# SCH_Lasercutter-Air-Control_2024-07-31.net
KiCad netlist of a schematic drawn in EasyEDA
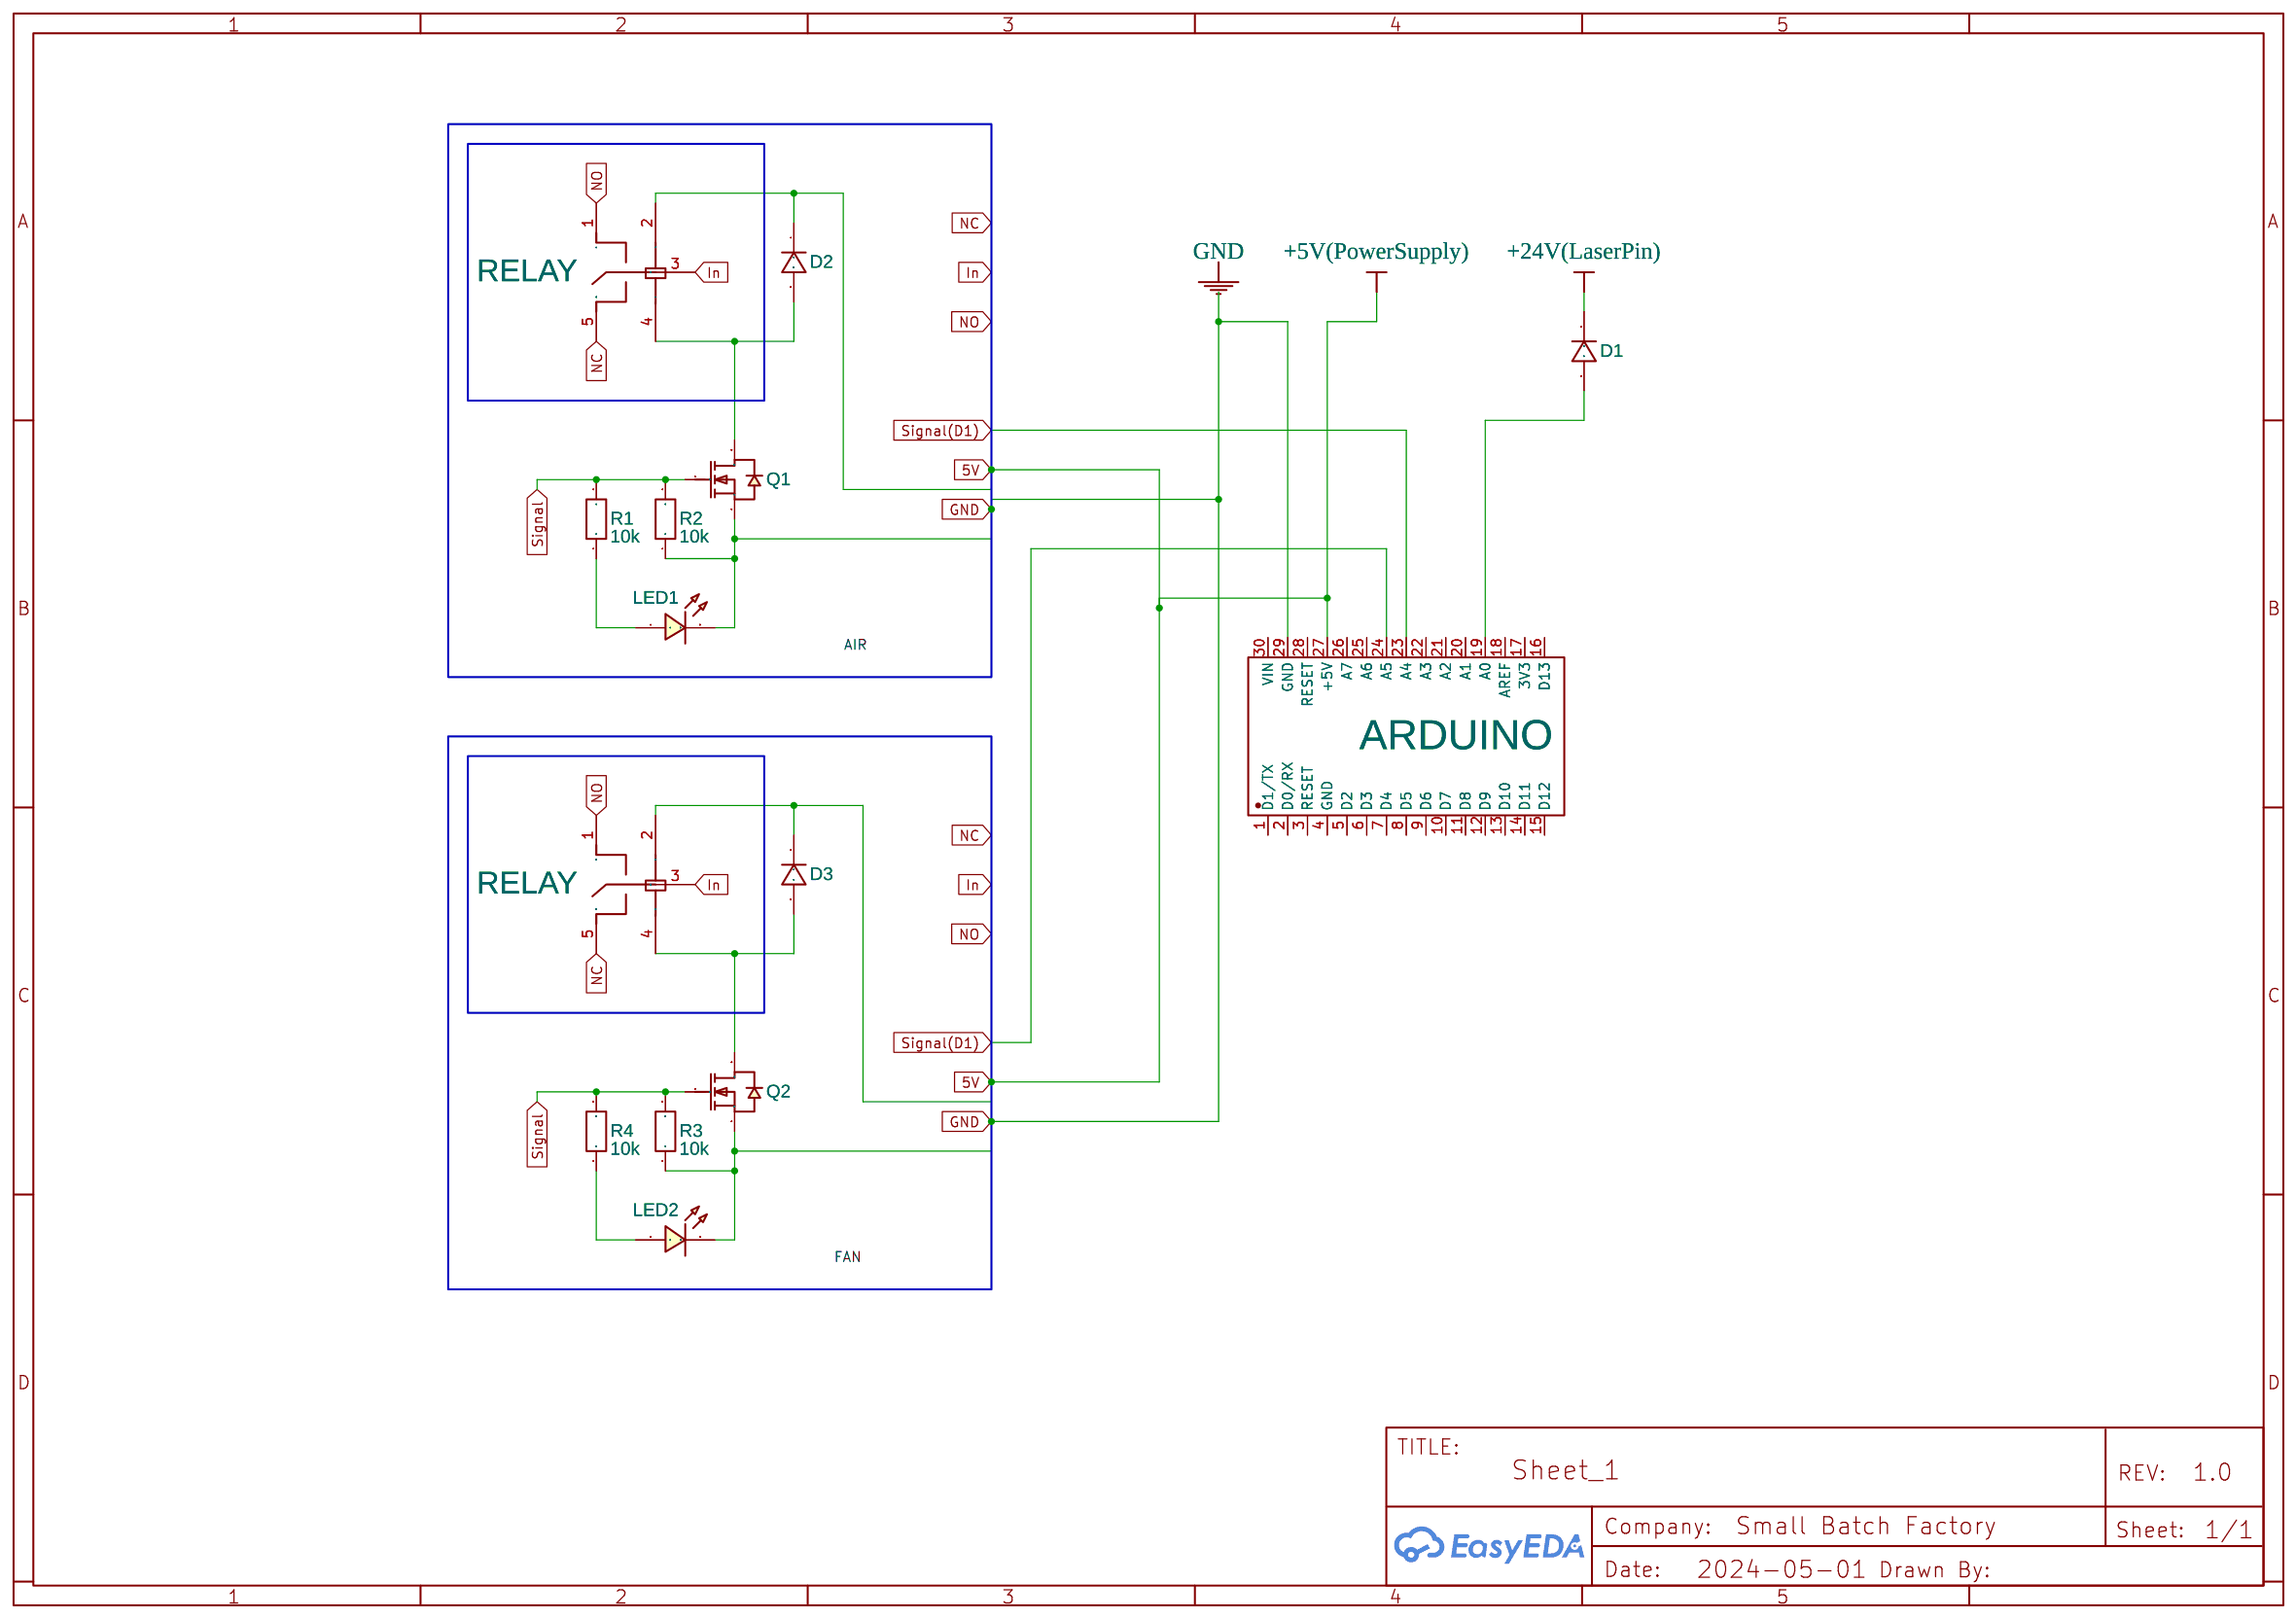
[diagram p0: schematic sheet]

(export (version "E")
  (design (tool "Eeschema 10.0.6"))
  (components
    (comp (ref "ARDUINO") (value "ARDUINO_NANO") (libsource (lib "") (part "ARDUINO_NANO")))
    (comp (ref "D1")
      (value "1N4007W")
      (fields (field (name "Manufacturer") "BLUE ROCKET"))
      (libsource (lib "") (part "1N4007W"))
    )
    (comp (ref "D2")
      (value "1N4007W")
      (fields (field (name "Manufacturer") "BLUE ROCKET"))
      (libsource (lib "") (part "1N4007W"))
    )
    (comp (ref "D3")
      (value "1N4007W")
      (fields (field (name "Manufacturer") "BLUE ROCKET"))
      (libsource (lib "") (part "1N4007W"))
    )
    (comp (ref "LED1")
      (value "LED-0603_R")
      (fields
        (field (name "Manufacturer Part") "19-217/R6C-AL1M2VY/3T")
        (field (name "Manufacturer") "EVERLIGHT(台湾亿光)")
      )
      (libsource (lib "") (part "LED-0603_R"))
    )
    (comp (ref "LED2")
      (value "LED-0603_R")
      (fields
        (field (name "Manufacturer Part") "19-217/R6C-AL1M2VY/3T")
        (field (name "Manufacturer") "EVERLIGHT(台湾亿光)")
      )
      (libsource (lib "") (part "LED-0603_R"))
    )
    (comp (ref "Q1")
      (value "2N7002")
      (fields (field (name "Manufacturer Part") "2N7002,215") (field (name "Manufacturer") "Nexperia"))
      (libsource (lib "") (part "2N7002"))
    )
    (comp (ref "Q2")
      (value "2N7002")
      (fields (field (name "Manufacturer Part") "2N7002,215") (field (name "Manufacturer") "Nexperia"))
      (libsource (lib "") (part "2N7002"))
    )
    (comp (ref "R1") (value "10k") (libsource (lib "") (part "R_0603_EU")))
    (comp (ref "R2") (value "10k") (libsource (lib "") (part "R_0603_EU")))
    (comp (ref "R3") (value "10k") (libsource (lib "") (part "R_0603_EU")))
    (comp (ref "R4") (value "10k") (libsource (lib "") (part "R_0603_EU")))
    (comp (ref "U2")
      (value "RELAY")
      (fields (field (name "Manufacturer Part") "Relay-SPST"))
      (libsource (lib "") (part "RELAY-SPST"))
    )
    (comp (ref "U3")
      (value "RELAY")
      (fields (field (name "Manufacturer Part") "Relay-SPST"))
      (libsource (lib "") (part "RELAY-SPST"))
    )
  )
  (nets
    (net (code "1") (name "+24V(LaserPin)") (class "Default")
      (node (ref "D1") (pin "1") (pinfunction "1_1") (pintype "unspecified"))
    )
    (net (code "4") (name "5V") (class "Default")
      (node (ref "ARDUINO") (pin "27") (pinfunction "+5V_27") (pintype "unspecified"))
      (node (ref "D2") (pin "1") (pinfunction "1_1") (pintype "unspecified"))
      (node (ref "D3") (pin "1") (pinfunction "1_1") (pintype "unspecified"))
      (node (ref "U2") (pin "2") (pinfunction "2_2") (pintype "unspecified"))
      (node (ref "U3") (pin "2") (pinfunction "2_2") (pintype "unspecified"))
    )
    (net (code "5") (name "GND") (class "Default")
      (node (ref "ARDUINO") (pin "29") (pinfunction "GND_29") (pintype "unspecified"))
      (node (ref "LED1") (pin "2") (pinfunction "2_2") (pintype "unspecified"))
      (node (ref "LED2") (pin "2") (pinfunction "2_2") (pintype "unspecified"))
      (node (ref "Q1") (pin "2") (pinfunction "S_2") (pintype "unspecified"))
      (node (ref "Q2") (pin "2") (pinfunction "S_2") (pintype "unspecified"))
      (node (ref "R2") (pin "1") (pinfunction "1_1") (pintype "unspecified"))
      (node (ref "R3") (pin "1") (pinfunction "1_1") (pintype "unspecified"))
    )
    (net (code "6") (name "In") (class "Default")
      (node (ref "U2") (pin "3") (pinfunction "3_3") (pintype "unspecified"))
      (node (ref "U3") (pin "3") (pinfunction "3_3") (pintype "unspecified"))
    )
    (net (code "7") (name "NC") (class "Default")
      (node (ref "U2") (pin "5") (pinfunction "5_5") (pintype "unspecified"))
      (node (ref "U3") (pin "5") (pinfunction "5_5") (pintype "unspecified"))
    )
    (net (code "8") (name "NO") (class "Default")
      (node (ref "U2") (pin "1") (pinfunction "1_1") (pintype "unspecified"))
      (node (ref "U3") (pin "1") (pinfunction "1_1") (pintype "unspecified"))
    )
    (net (code "9") (name "Net-(ARDUINO-A0)") (class "Default")
      (node (ref "ARDUINO") (pin "19") (pinfunction "A0_19") (pintype "unspecified"))
      (node (ref "D1") (pin "2") (pinfunction "2_2") (pintype "unspecified"))
    )
    (net (code "10") (name "Net-(LED1-Pad1)") (class "Default")
      (node (ref "LED1") (pin "1") (pinfunction "1_1") (pintype "unspecified"))
      (node (ref "R1") (pin "1") (pinfunction "1_1") (pintype "unspecified"))
    )
    (net (code "11") (name "Net-(LED2-Pad1)") (class "Default")
      (node (ref "LED2") (pin "1") (pinfunction "1_1") (pintype "unspecified"))
      (node (ref "R4") (pin "1") (pinfunction "1_1") (pintype "unspecified"))
    )
    (net (code "12") (name "Net-(Q1-D)") (class "Default")
      (node (ref "D2") (pin "2") (pinfunction "2_2") (pintype "unspecified"))
      (node (ref "Q1") (pin "3") (pinfunction "D_3") (pintype "unspecified"))
      (node (ref "U2") (pin "4") (pinfunction "4_4") (pintype "unspecified"))
    )
    (net (code "13") (name "Net-(Q2-D)") (class "Default")
      (node (ref "D3") (pin "2") (pinfunction "2_2") (pintype "unspecified"))
      (node (ref "Q2") (pin "3") (pinfunction "D_3") (pintype "unspecified"))
      (node (ref "U3") (pin "4") (pinfunction "4_4") (pintype "unspecified"))
    )
    (net (code "14") (name "Signal") (class "Default")
      (node (ref "Q1") (pin "1") (pinfunction "G_1") (pintype "unspecified"))
      (node (ref "Q2") (pin "1") (pinfunction "G_1") (pintype "unspecified"))
      (node (ref "R1") (pin "2") (pinfunction "2_2") (pintype "unspecified"))
      (node (ref "R2") (pin "2") (pinfunction "2_2") (pintype "unspecified"))
      (node (ref "R3") (pin "2") (pinfunction "2_2") (pintype "unspecified"))
      (node (ref "R4") (pin "2") (pinfunction "2_2") (pintype "unspecified"))
    )
    (net (code "15") (name "Signal(D1)") (class "Default")
      (node (ref "ARDUINO") (pin "23") (pinfunction "A4_23") (pintype "unspecified"))
      (node (ref "ARDUINO") (pin "24") (pinfunction "A5_24") (pintype "unspecified"))
    )
    (net (code "16") (name "unconnected-(ARDUINO-3V3-Pad17)") (class "Default")
      (node (ref "ARDUINO") (pin "17") (pinfunction "3V3_17") (pintype "unspecified"))
    )
    (net (code "17") (name "unconnected-(ARDUINO-A1-Pad20)") (class "Default")
      (node (ref "ARDUINO") (pin "20") (pinfunction "A1_20") (pintype "unspecified"))
    )
    (net (code "18") (name "unconnected-(ARDUINO-A2-Pad21)") (class "Default")
      (node (ref "ARDUINO") (pin "21") (pinfunction "A2_21") (pintype "unspecified"))
    )
    (net (code "19") (name "unconnected-(ARDUINO-A3-Pad22)") (class "Default")
      (node (ref "ARDUINO") (pin "22") (pinfunction "A3_22") (pintype "unspecified"))
    )
    (net (code "20") (name "unconnected-(ARDUINO-A6-Pad25)") (class "Default")
      (node (ref "ARDUINO") (pin "25") (pinfunction "A6_25") (pintype "unspecified"))
    )
    (net (code "21") (name "unconnected-(ARDUINO-A7-Pad26)") (class "Default")
      (node (ref "ARDUINO") (pin "26") (pinfunction "A7_26") (pintype "unspecified"))
    )
    (net (code "22") (name "unconnected-(ARDUINO-AREF-Pad18)") (class "Default")
      (node (ref "ARDUINO") (pin "18") (pinfunction "AREF_18") (pintype "unspecified"))
    )
    (net (code "23") (name "unconnected-(ARDUINO-D0{slash}RX-Pad2)") (class "Default")
      (node (ref "ARDUINO") (pin "2") (pinfunction "D0/RX_2") (pintype "unspecified"))
    )
    (net (code "24") (name "unconnected-(ARDUINO-D1{slash}TX-Pad1)") (class "Default")
      (node (ref "ARDUINO") (pin "1") (pinfunction "D1/TX_1") (pintype "unspecified"))
    )
    (net (code "25") (name "unconnected-(ARDUINO-D2-Pad5)") (class "Default")
      (node (ref "ARDUINO") (pin "5") (pinfunction "D2_5") (pintype "unspecified"))
    )
    (net (code "26") (name "unconnected-(ARDUINO-D3-Pad6)") (class "Default")
      (node (ref "ARDUINO") (pin "6") (pinfunction "D3_6") (pintype "unspecified"))
    )
    (net (code "27") (name "unconnected-(ARDUINO-D4-Pad7)") (class "Default")
      (node (ref "ARDUINO") (pin "7") (pinfunction "D4_7") (pintype "unspecified"))
    )
    (net (code "28") (name "unconnected-(ARDUINO-D5-Pad8)") (class "Default")
      (node (ref "ARDUINO") (pin "8") (pinfunction "D5_8") (pintype "unspecified"))
    )
    (net (code "29") (name "unconnected-(ARDUINO-D6-Pad9)") (class "Default")
      (node (ref "ARDUINO") (pin "9") (pinfunction "D6_9") (pintype "unspecified"))
    )
    (net (code "30") (name "unconnected-(ARDUINO-D7-Pad10)") (class "Default")
      (node (ref "ARDUINO") (pin "10") (pinfunction "D7_10") (pintype "unspecified"))
    )
    (net (code "31") (name "unconnected-(ARDUINO-D8-Pad11)") (class "Default")
      (node (ref "ARDUINO") (pin "11") (pinfunction "D8_11") (pintype "unspecified"))
    )
    (net (code "32") (name "unconnected-(ARDUINO-D9-Pad12)") (class "Default")
      (node (ref "ARDUINO") (pin "12") (pinfunction "D9_12") (pintype "unspecified"))
    )
    (net (code "33") (name "unconnected-(ARDUINO-D10-Pad13)") (class "Default")
      (node (ref "ARDUINO") (pin "13") (pinfunction "D10_13") (pintype "unspecified"))
    )
    (net (code "34") (name "unconnected-(ARDUINO-D11-Pad14)") (class "Default")
      (node (ref "ARDUINO") (pin "14") (pinfunction "D11_14") (pintype "unspecified"))
    )
    (net (code "35") (name "unconnected-(ARDUINO-D12-Pad15)") (class "Default")
      (node (ref "ARDUINO") (pin "15") (pinfunction "D12_15") (pintype "unspecified"))
    )
    (net (code "36") (name "unconnected-(ARDUINO-D13-Pad16)") (class "Default")
      (node (ref "ARDUINO") (pin "16") (pinfunction "D13_16") (pintype "unspecified"))
    )
    (net (code "37") (name "unconnected-(ARDUINO-GND-Pad4)") (class "Default")
      (node (ref "ARDUINO") (pin "4") (pinfunction "GND_4") (pintype "unspecified"))
    )
    (net (code "38") (name "unconnected-(ARDUINO-RESET-Pad3)") (class "Default")
      (node (ref "ARDUINO") (pin "3") (pinfunction "RESET_3") (pintype "unspecified"))
    )
    (net (code "39") (name "unconnected-(ARDUINO-RESET-Pad28)") (class "Default")
      (node (ref "ARDUINO") (pin "28") (pinfunction "RESET_28") (pintype "unspecified"))
    )
    (net (code "40") (name "unconnected-(ARDUINO-VIN-Pad30)") (class "Default")
      (node (ref "ARDUINO") (pin "30") (pinfunction "VIN_30") (pintype "unspecified"))
    )
  )
)
